# NTcounterTX.net
KiCad netlist of a schematic drawn in EAGLE
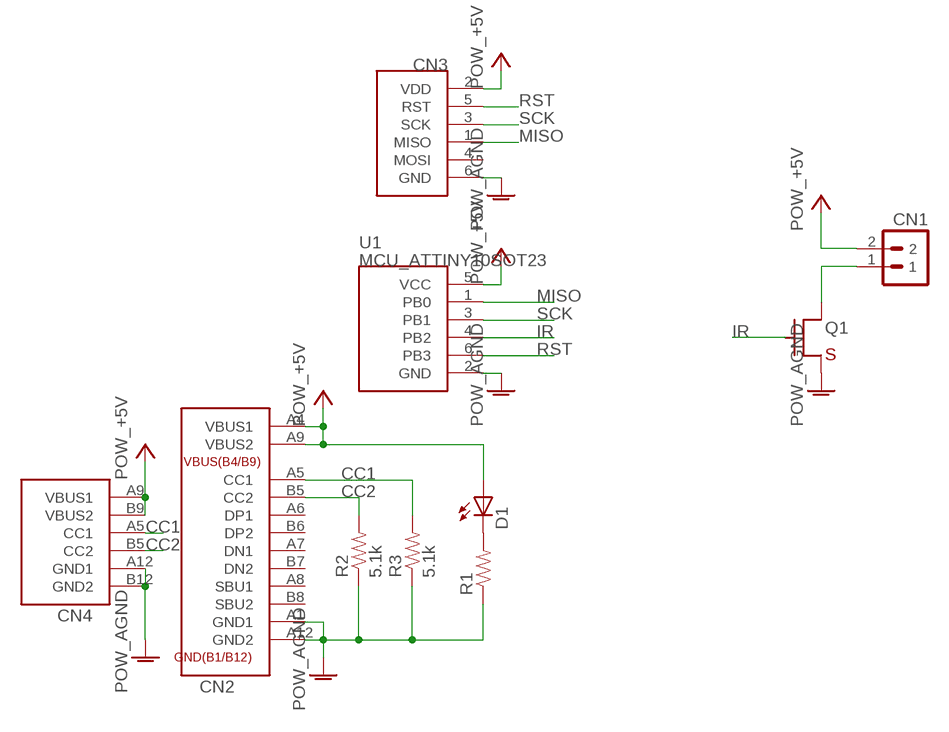
[diagram p0: schematic, sheet 1]

(export (version "E")
  (design (tool "Eeschema 10.0.6"))
  (components
    (comp (ref "CN1")
      (value "CON_PINHD-1X2LOCK")
      (footprint "eagle-import:SPARKFUN_1X02_LOCK")
      (libsource (lib "eagle-import") (part "CON_PINHD-1X2LOCK"))
    )
    (comp (ref "CN2")
      (value "CON_USB-C-16TH")
      (footprint "eagle-import:USB-C_16P_TH")
      (libsource (lib "eagle-import") (part "CON_USB-C-16TH"))
    )
    (comp (ref "CN3")
      (value "CON_AVRISPTH")
      (footprint "eagle-import:2X03R")
      (libsource (lib "eagle-import") (part "CON_AVRISPTH"))
    )
    (comp (ref "CN4")
      (value "CON_USB-C-6")
      (footprint "eagle-import:USB-C_6P")
      (libsource (lib "eagle-import") (part "CON_USB-C-6"))
    )
    (comp (ref "D1")
      (value "LED0603")
      (footprint "eagle-import:SPARKFUN_LED-0603")
      (libsource (lib "eagle-import") (part "LED0603"))
    )
    (comp (ref "Q1")
      (value "TR_NMOS_IRLML6344")
      (footprint "eagle-import:SOT-23-3-2916")
      (libsource (lib "eagle-import") (part "TR_NMOS_IRLML6344"))
    )
    (comp (ref "R1")
      (value "RES0603")
      (footprint "eagle-import:0603")
      (libsource (lib "eagle-import") (part "RES0603"))
    )
    (comp (ref "R2")
      (value "5.1k")
      (footprint "eagle-import:0603")
      (libsource (lib "eagle-import") (part "RES0603"))
    )
    (comp (ref "R3")
      (value "5.1k")
      (footprint "eagle-import:0603")
      (libsource (lib "eagle-import") (part "RES0603"))
    )
    (comp (ref "U1")
      (value "MCU_ATTINY10SOT23")
      (footprint "eagle-import:SOT23-6")
      (libsource (lib "eagle-import") (part "MCU_ATTINY10SOT23"))
    )
  )
  (nets
    (net (code "1") (name "/CC1") (class "Default")
      (node (ref "CN2") (pin "A5") (pinfunction "CC1_A5") (pintype "bidirectional"))
      (node (ref "CN4") (pin "A5") (pinfunction "CC1_A5") (pintype "bidirectional"))
      (node (ref "R3") (pin "2") (pinfunction "2_2") (pintype "passive"))
    )
    (net (code "2") (name "/CC2") (class "Default")
      (node (ref "CN2") (pin "B5") (pinfunction "CC2_B5") (pintype "bidirectional"))
      (node (ref "CN4") (pin "B5") (pinfunction "CC2_B5") (pintype "bidirectional"))
      (node (ref "R2") (pin "2") (pinfunction "2_2") (pintype "passive"))
    )
    (net (code "3") (name "/IR") (class "Default")
      (node (ref "Q1") (pin "1") (pinfunction "G_1") (pintype "bidirectional"))
      (node (ref "U1") (pin "4") (pinfunction "PB2_4") (pintype "bidirectional"))
    )
    (net (code "4") (name "/MISO") (class "Default")
      (node (ref "CN3") (pin "1") (pinfunction "MISO_1") (pintype "bidirectional"))
      (node (ref "U1") (pin "1") (pinfunction "PB0_1") (pintype "bidirectional"))
    )
    (net (code "5") (name "/RST") (class "Default")
      (node (ref "CN3") (pin "5") (pinfunction "RST_5") (pintype "bidirectional"))
      (node (ref "U1") (pin "6") (pinfunction "PB3_6") (pintype "bidirectional"))
    )
    (net (code "6") (name "/SCK") (class "Default")
      (node (ref "CN3") (pin "3") (pinfunction "SCK_3") (pintype "bidirectional"))
      (node (ref "U1") (pin "3") (pinfunction "PB1_3") (pintype "bidirectional"))
    )
    (net (code "7") (name "Net-(D1-PadC)") (class "Default")
      (node (ref "D1") (pin "C") (pinfunction "C_C") (pintype "passive"))
      (node (ref "R1") (pin "2") (pinfunction "2_2") (pintype "passive"))
    )
    (net (code "8") (name "Net-(Q1-D)") (class "Default")
      (node (ref "CN1") (pin "1") (pinfunction "1_1") (pintype "passive"))
      (node (ref "Q1") (pin "3") (pinfunction "D_3") (pintype "bidirectional"))
    )
    (net (code "9") (name "POW_+5V") (class "Default")
      (node (ref "CN1") (pin "2") (pinfunction "2_2") (pintype "passive"))
      (node (ref "CN2") (pin "A4") (pinfunction "VBUS1_A4") (pintype "bidirectional"))
      (node (ref "CN2") (pin "A9") (pinfunction "VBUS2_A9") (pintype "bidirectional"))
      (node (ref "CN3") (pin "2") (pinfunction "VDD_2") (pintype "bidirectional"))
      (node (ref "CN4") (pin "A9") (pinfunction "VBUS1_A9") (pintype "bidirectional"))
      (node (ref "CN4") (pin "B9") (pinfunction "VBUS2_B9") (pintype "bidirectional"))
      (node (ref "D1") (pin "A") (pinfunction "A_A") (pintype "passive"))
      (node (ref "U1") (pin "5") (pinfunction "VCC_5") (pintype "bidirectional"))
    )
    (net (code "10") (name "POW_AGND") (class "Default")
      (node (ref "CN2") (pin "A1") (pinfunction "GND1_A1") (pintype "bidirectional"))
      (node (ref "CN2") (pin "A12") (pinfunction "GND2_A12") (pintype "bidirectional"))
      (node (ref "CN3") (pin "6") (pinfunction "GND_6") (pintype "bidirectional"))
      (node (ref "CN4") (pin "A12") (pinfunction "GND1_A12") (pintype "bidirectional"))
      (node (ref "CN4") (pin "B12") (pinfunction "GND2_B12") (pintype "bidirectional"))
      (node (ref "Q1") (pin "2") (pinfunction "S_2") (pintype "bidirectional"))
      (node (ref "R1") (pin "1") (pinfunction "1_1") (pintype "passive"))
      (node (ref "R2") (pin "1") (pinfunction "1_1") (pintype "passive"))
      (node (ref "R3") (pin "1") (pinfunction "1_1") (pintype "passive"))
      (node (ref "U1") (pin "2") (pinfunction "GND_2") (pintype "bidirectional"))
    )
    (net (code "11") (name "unconnected-(CN2-DN1-PadA7)") (class "Default")
      (node (ref "CN2") (pin "A7") (pinfunction "DN1_A7") (pintype "bidirectional"))
    )
    (net (code "12") (name "unconnected-(CN2-DN2-PadB7)") (class "Default")
      (node (ref "CN2") (pin "B7") (pinfunction "DN2_B7") (pintype "bidirectional"))
    )
    (net (code "13") (name "unconnected-(CN2-DP1-PadA6)") (class "Default")
      (node (ref "CN2") (pin "A6") (pinfunction "DP1_A6") (pintype "bidirectional"))
    )
    (net (code "14") (name "unconnected-(CN2-DP2-PadB6)") (class "Default")
      (node (ref "CN2") (pin "B6") (pinfunction "DP2_B6") (pintype "bidirectional"))
    )
    (net (code "15") (name "unconnected-(CN2-SBU1-PadA8)") (class "Default")
      (node (ref "CN2") (pin "A8") (pinfunction "SBU1_A8") (pintype "bidirectional"))
    )
    (net (code "16") (name "unconnected-(CN2-SBU2-PadB8)") (class "Default")
      (node (ref "CN2") (pin "B8") (pinfunction "SBU2_B8") (pintype "bidirectional"))
    )
    (net (code "17") (name "unconnected-(CN3-MOSI-Pad4)") (class "Default")
      (node (ref "CN3") (pin "4") (pinfunction "MOSI_4") (pintype "bidirectional"))
    )
  )
)
